# light_sensor_basic.net
KiCad netlist of a schematic drawn in EAGLE
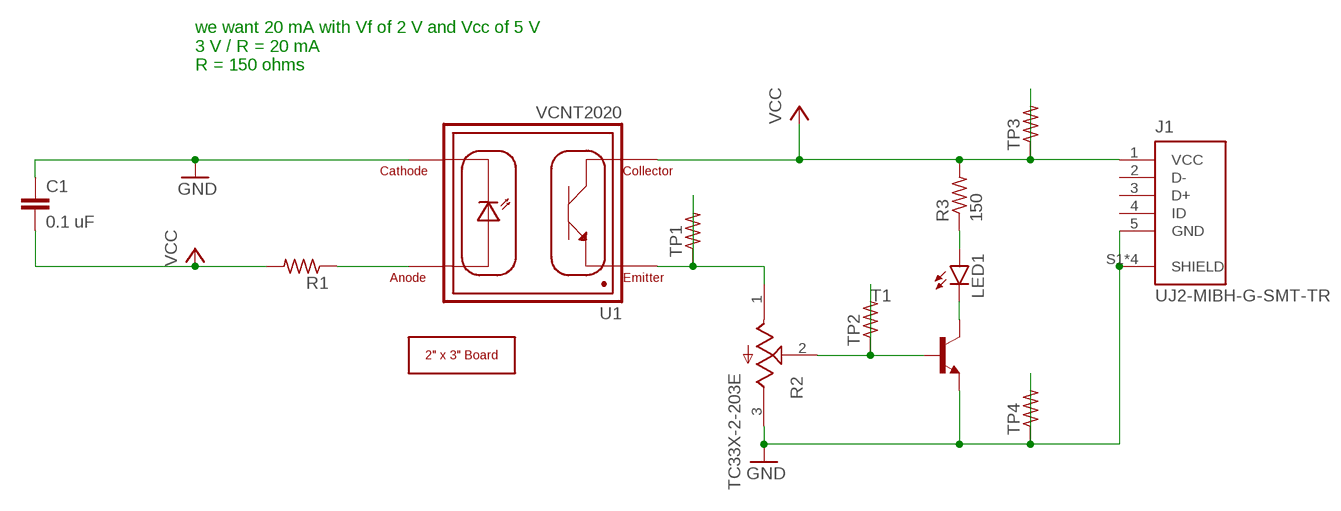
[diagram p0: schematic, sheet 1]

(export (version "E")
  (design (tool "Eeschema 10.0.6"))
  (components
    (comp (ref "C1")
      (value "0.1 uF")
      (footprint "eagle-import:C1206")
      (libsource (lib "eagle-import") (part "C-EUC1206"))
    )
    (comp (ref "J1")
      (value "UJ2-MIBH-G-SMT-TR")
      (footprint "eagle-import:CUI_UJ2-MIBH-G-SMT-TR")
      (fields (field (name "MANUFACTURER") "CUI"))
      (libsource (lib "eagle-import") (part "UJ2-MIBH-G-SMT-TR"))
    )
    (comp (ref "LED1")
      (value "LEDSML0805")
      (footprint "eagle-import:SML0805")
      (libsource (lib "eagle-import") (part "LEDSML0805"))
    )
    (comp (ref "R1")
      (value "R-US_R0805")
      (footprint "eagle-import:R0805")
      (libsource (lib "eagle-import") (part "R-US_R0805"))
    )
    (comp (ref "R2")
      (value "TC33X-2-203E")
      (footprint "eagle-import:TRIM_TC33X-2-203E")
      (fields (field (name "DIGIKEY_PART_NUMBER") "TC33X-2-203ETR-ND") (field (name "MF") "Bourns"))
      (libsource (lib "eagle-import") (part "TC33X-2-203E"))
    )
    (comp (ref "R3")
      (value "150")
      (footprint "eagle-import:R0805")
      (libsource (lib "eagle-import") (part "R-US_R0805"))
    )
    (comp (ref "T1")
      (value "BC817-NPN-SOT23-BEC")
      (footprint "eagle-import:SOT23-BEC")
      (libsource (lib "eagle-import") (part "-NPN-SOT23-BECBC817"))
    )
    (comp (ref "TP1")
      (value "R-US_R1206")
      (footprint "eagle-import:R1206")
      (libsource (lib "eagle-import") (part "R-US_R1206"))
    )
    (comp (ref "TP2")
      (value "R-US_R1206")
      (footprint "eagle-import:R1206")
      (libsource (lib "eagle-import") (part "R-US_R1206"))
    )
    (comp (ref "TP3")
      (value "R-US_R1206")
      (footprint "eagle-import:R1206")
      (libsource (lib "eagle-import") (part "R-US_R1206"))
    )
    (comp (ref "TP4")
      (value "R-US_R1206")
      (footprint "eagle-import:R1206")
      (libsource (lib "eagle-import") (part "R-US_R1206"))
    )
    (comp (ref "U$1")
      (value "2X3_BOARD_V2")
      (footprint "eagle-import:2X3_BOARD_V2")
      (libsource (lib "eagle-import") (part "2X3_BOARD_V2"))
    )
    (comp (ref "U1")
      (value "VCNT2020")
      (footprint "eagle-import:XDCR_VCNT2020")
      (fields (field (name "DIGIKEY_PART_NUMBER") "VCNT2020TR-ND") (field (name "MF") "Vishay"))
      (libsource (lib "eagle-import") (part "VCNT2020"))
    )
  )
  (nets
    (net (code "1") (name "GND") (class "Default")
      (node (ref "C1") (pin "1") (pinfunction "1_1") (pintype "passive"))
      (node (ref "J1") (pin "5") (pinfunction "GND_5") (pintype "power_in"))
      (node (ref "J1") (pin "S1") (pinfunction "SHIELD_S1") (pintype "passive"))
      (node (ref "J1") (pin "S2") (pinfunction "SHIELD_S2") (pintype "passive"))
      (node (ref "J1") (pin "S3") (pinfunction "SHIELD_S3") (pintype "passive"))
      (node (ref "J1") (pin "S4") (pinfunction "SHIELD_S4") (pintype "passive"))
      (node (ref "R2") (pin "3") (pinfunction "CW_3") (pintype "passive"))
      (node (ref "T1") (pin "E") (pinfunction "E_E") (pintype "passive"))
      (node (ref "TP4") (pin "1") (pinfunction "1_1") (pintype "passive"))
      (node (ref "TP4") (pin "2") (pinfunction "2_2") (pintype "passive"))
      (node (ref "U1") (pin "4") (pinfunction "CATHODE_4") (pintype "passive"))
    )
    (net (code "2") (name "Net-(LED1-PadA)") (class "Default")
      (node (ref "LED1") (pin "A") (pinfunction "A_A") (pintype "passive"))
      (node (ref "R3") (pin "1") (pinfunction "1_1") (pintype "passive"))
    )
    (net (code "3") (name "Net-(LED1-PadC)") (class "Default")
      (node (ref "LED1") (pin "C") (pinfunction "C_C") (pintype "passive"))
      (node (ref "T1") (pin "C") (pinfunction "C_C") (pintype "passive"))
    )
    (net (code "4") (name "Net-(R2-CCW)") (class "Default")
      (node (ref "R2") (pin "1") (pinfunction "CCW_1") (pintype "passive"))
      (node (ref "TP1") (pin "1") (pinfunction "1_1") (pintype "passive"))
      (node (ref "TP1") (pin "2") (pinfunction "2_2") (pintype "passive"))
      (node (ref "U1") (pin "1") (pinfunction "EMITTER_1") (pintype "passive"))
    )
    (net (code "5") (name "Net-(R2-W)") (class "Default")
      (node (ref "R2") (pin "2") (pinfunction "W_2") (pintype "passive"))
      (node (ref "T1") (pin "B") (pinfunction "B_B") (pintype "passive"))
      (node (ref "TP2") (pin "1") (pinfunction "1_1") (pintype "passive"))
      (node (ref "TP2") (pin "2") (pinfunction "2_2") (pintype "passive"))
    )
    (net (code "6") (name "Net-(U1-ANODE)") (class "Default")
      (node (ref "R1") (pin "1") (pinfunction "1_1") (pintype "passive"))
      (node (ref "U1") (pin "3") (pinfunction "ANODE_3") (pintype "passive"))
    )
    (net (code "7") (name "VCC") (class "Default")
      (node (ref "C1") (pin "2") (pinfunction "2_2") (pintype "passive"))
      (node (ref "J1") (pin "1") (pinfunction "VCC_1") (pintype "power_in"))
      (node (ref "R1") (pin "2") (pinfunction "2_2") (pintype "passive"))
      (node (ref "R3") (pin "2") (pinfunction "2_2") (pintype "passive"))
      (node (ref "TP3") (pin "1") (pinfunction "1_1") (pintype "passive"))
      (node (ref "TP3") (pin "2") (pinfunction "2_2") (pintype "passive"))
      (node (ref "U1") (pin "2") (pinfunction "COLLECTOR_2") (pintype "passive"))
    )
    (net (code "8") (name "unconnected-(J1-D+-Pad3)") (class "Default")
      (node (ref "J1") (pin "3") (pinfunction "D+_3") (pintype "bidirectional"))
    )
    (net (code "9") (name "unconnected-(J1-D--Pad2)") (class "Default")
      (node (ref "J1") (pin "2") (pinfunction "D-_2") (pintype "bidirectional"))
    )
    (net (code "10") (name "unconnected-(J1-ID-Pad4)") (class "Default")
      (node (ref "J1") (pin "4") (pinfunction "ID_4") (pintype "bidirectional"))
    )
  )
)
